# Fake_Alarm.net
KiCad netlist of a schematic drawn in EAGLE
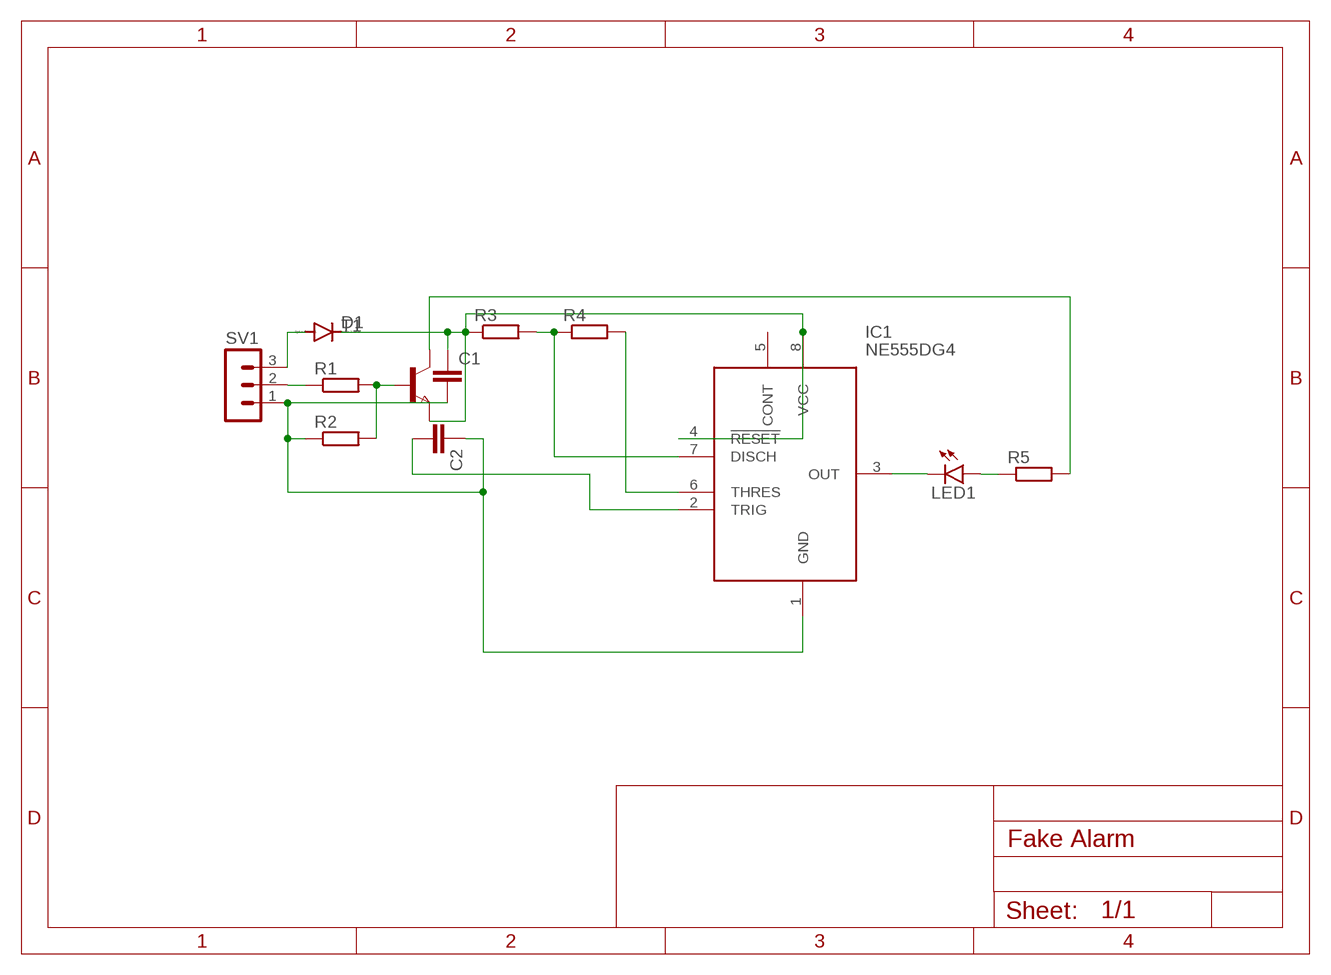
[diagram p0: schematic, sheet 1]

(export (version "E")
  (design (tool "Eeschema 10.0.6"))
  (components
    (comp (ref "C1")
      (value "C-EUC0805")
      (footprint "eagle-import:C0805")
      (libsource (lib "eagle-import") (part "C-EUC0805"))
    )
    (comp (ref "C2")
      (value "C-EUC0805")
      (footprint "eagle-import:C0805")
      (libsource (lib "eagle-import") (part "C-EUC0805"))
    )
    (comp (ref "D1")
      (value "DIODE-DO-214AC")
      (footprint "eagle-import:DO-214AC")
      (libsource (lib "eagle-import") (part "DIODE-DO-214AC"))
    )
    (comp (ref "IC1")
      (value "NE555DG4")
      (footprint "eagle-import:SOIC127P600X175-8N")
      (fields (field (name "MOUSER_PART_NUMBER") "595-NE555DG4"))
      (libsource (lib "eagle-import") (part "NE555DG4"))
    )
    (comp (ref "LED1")
      (value "LEDKA-3528ASYC")
      (footprint "eagle-import:KA-3528ASYC")
      (libsource (lib "eagle-import") (part "LEDKA-3528ASYC"))
    )
    (comp (ref "R1")
      (value "R-EU_M0805")
      (footprint "eagle-import:M0805")
      (libsource (lib "eagle-import") (part "R-EU_M0805"))
    )
    (comp (ref "R2")
      (value "R-EU_M0805")
      (footprint "eagle-import:M0805")
      (libsource (lib "eagle-import") (part "R-EU_M0805"))
    )
    (comp (ref "R3")
      (value "R-EU_M0805")
      (footprint "eagle-import:M0805")
      (libsource (lib "eagle-import") (part "R-EU_M0805"))
    )
    (comp (ref "R4")
      (value "R-EU_M0805")
      (footprint "eagle-import:M0805")
      (libsource (lib "eagle-import") (part "R-EU_M0805"))
    )
    (comp (ref "R5")
      (value "R-EU_M0805")
      (footprint "eagle-import:M0805")
      (libsource (lib "eagle-import") (part "R-EU_M0805"))
    )
    (comp (ref "SV1")
      (value "MA03-1")
      (footprint "eagle-import:MA03-1")
      (libsource (lib "eagle-import") (part "MA03-1"))
    )
    (comp (ref "T1")
      (value "NPNSOT23")
      (footprint "eagle-import:SOT-23")
      (fields (field (name "MPN") "DSS20201L-7"))
      (libsource (lib "eagle-import") (part "NPNSOT23"))
    )
  )
  (nets
    (net (code "1") (name "Net-(D1-PadA)") (class "Default")
      (node (ref "D1") (pin "A") (pinfunction "A_A") (pintype "passive"))
      (node (ref "SV1") (pin "3") (pinfunction "3_3") (pintype "passive"))
    )
    (net (code "2") (name "Net-(IC1-DISCH)") (class "Default")
      (node (ref "IC1") (pin "7") (pinfunction "DISCH_7") (pintype "bidirectional"))
      (node (ref "R3") (pin "2") (pinfunction "2_2") (pintype "passive"))
      (node (ref "R4") (pin "1") (pinfunction "1_1") (pintype "passive"))
    )
    (net (code "3") (name "Net-(IC1-GND)") (class "Default")
      (node (ref "C1") (pin "2") (pinfunction "2_2") (pintype "passive"))
      (node (ref "C2") (pin "1") (pinfunction "1_1") (pintype "passive"))
      (node (ref "IC1") (pin "1") (pinfunction "GND_1") (pintype "bidirectional"))
      (node (ref "R2") (pin "1") (pinfunction "1_1") (pintype "passive"))
      (node (ref "SV1") (pin "1") (pinfunction "1_1") (pintype "passive"))
    )
    (net (code "4") (name "Net-(IC1-OUT)") (class "Default")
      (node (ref "IC1") (pin "3") (pinfunction "OUT_3") (pintype "bidirectional"))
      (node (ref "LED1") (pin "C") (pinfunction "C_C") (pintype "passive"))
    )
    (net (code "5") (name "Net-(IC1-THRES)") (class "Default")
      (node (ref "IC1") (pin "6") (pinfunction "THRES_6") (pintype "bidirectional"))
      (node (ref "R4") (pin "2") (pinfunction "2_2") (pintype "passive"))
    )
    (net (code "6") (name "Net-(IC1-TRIG)") (class "Default")
      (node (ref "C2") (pin "2") (pinfunction "2_2") (pintype "passive"))
      (node (ref "IC1") (pin "2") (pinfunction "TRIG_2") (pintype "bidirectional"))
    )
    (net (code "7") (name "Net-(IC1-VCC)") (class "Default")
      (node (ref "C1") (pin "1") (pinfunction "1_1") (pintype "passive"))
      (node (ref "D1") (pin "C") (pinfunction "C_C") (pintype "passive"))
      (node (ref "IC1") (pin "4") (pinfunction "~{RESET}_4") (pintype "bidirectional"))
      (node (ref "IC1") (pin "8") (pinfunction "VCC_8") (pintype "bidirectional"))
      (node (ref "R3") (pin "1") (pinfunction "1_1") (pintype "passive"))
      (node (ref "T1") (pin "2") (pinfunction "E_2") (pintype "passive"))
    )
    (net (code "8") (name "Net-(LED1-PadA)") (class "Default")
      (node (ref "LED1") (pin "A") (pinfunction "A_A") (pintype "passive"))
      (node (ref "R5") (pin "1") (pinfunction "1_1") (pintype "passive"))
    )
    (net (code "9") (name "Net-(R1-Pad1)") (class "Default")
      (node (ref "R1") (pin "1") (pinfunction "1_1") (pintype "passive"))
      (node (ref "SV1") (pin "2") (pinfunction "2_2") (pintype "passive"))
    )
    (net (code "10") (name "Net-(T1-B)") (class "Default")
      (node (ref "R1") (pin "2") (pinfunction "2_2") (pintype "passive"))
      (node (ref "R2") (pin "2") (pinfunction "2_2") (pintype "passive"))
      (node (ref "T1") (pin "3") (pinfunction "B_3") (pintype "passive"))
    )
    (net (code "11") (name "Net-(T1-C)") (class "Default")
      (node (ref "R5") (pin "2") (pinfunction "2_2") (pintype "passive"))
      (node (ref "T1") (pin "1") (pinfunction "C_1") (pintype "passive"))
    )
    (net (code "12") (name "unconnected-(IC1-CONT-Pad5)") (class "Default")
      (node (ref "IC1") (pin "5") (pinfunction "CONT_5") (pintype "bidirectional"))
    )
  )
)
